# STM32F4_OSD_V13.net
KiCad netlist of a schematic drawn in Altium Designer
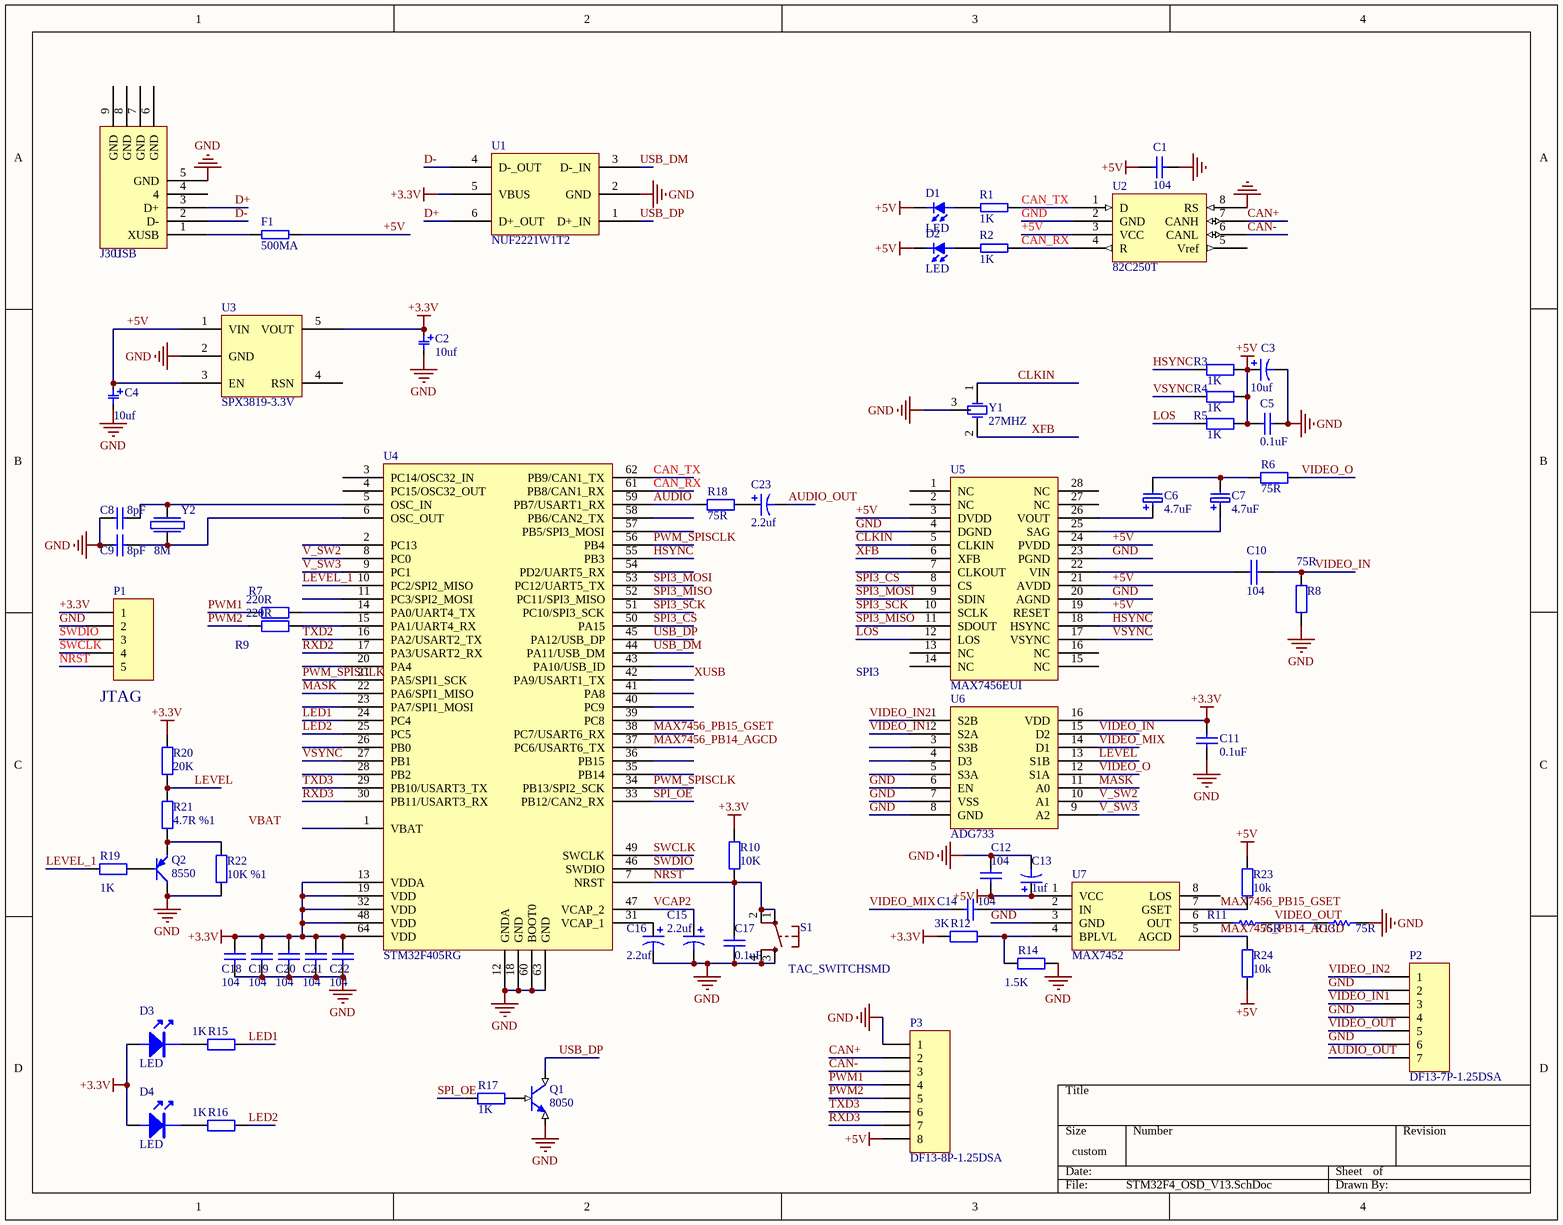
[diagram p0: STM32F4_OSD_V13.SchDoc]

(export (version "E")
  (design (tool "Eeschema 10.0.6"))
  (components
    (comp (ref "C1")
      (value "104")
      (footprint "0603C")
      (description "Capacitor")
      (fields (field (name "PUBLISHER") "Altium Limited"))
      (libsource (lib "*") (part "CAP"))
    )
    (comp (ref "C2") (value "10uf") (footprint "0805") (libsource (lib "电阻电容") (part "ECAP")))
    (comp (ref "C3")
      (value "10uf")
      (footprint "0603C")
      (description "Polarized Capacitor (Radial)")
      (libsource (lib "Miscellaneous Devices") (part "Cap Pol1"))
    )
    (comp (ref "C4") (value "10uf") (footprint "0805") (libsource (lib "电阻电容") (part "ECAP")))
    (comp (ref "C5")
      (value "0.1uF")
      (footprint "0402-CAP")
      (description "Capacitor")
      (fields (field (name "Comment") "Cap") (field (name "PUBLISHER") "Altium Limited"))
      (libsource (lib "Miscellaneous Devices") (part "Cap"))
    )
    (comp (ref "C6")
      (value "4.7uF")
      (footprint "0603C")
      (description "Electrolytic Capacitor 1")
      (libsource (lib "QT_SCH_V2") (part "ELECTRO1"))
    )
    (comp (ref "C7")
      (value "4.7uF")
      (footprint "0603C")
      (description "Electrolytic Capacitor 1")
      (libsource (lib "QT_SCH_V2") (part "ELECTRO1"))
    )
    (comp (ref "C8")
      (value "8pF")
      (footprint "0402-CAP")
      (description "Capacitor")
      (libsource (lib "EMotus Components") (part "CAP0805"))
    )
    (comp (ref "C9")
      (value "8pF")
      (footprint "0402-CAP")
      (description "Capacitor")
      (libsource (lib "EMotus Components") (part "CAP0805"))
    )
    (comp (ref "C10")
      (value "104")
      (footprint "0402-CAP")
      (description "Capacitor")
      (libsource (lib "") (part "CAP_1"))
    )
    (comp (ref "C11")
      (value "0.1uF")
      (footprint "0402-CAP")
      (description "Capacitor")
      (fields (field (name "Comment") "Cap") (field (name "PUBLISHER") "Altium Limited"))
      (libsource (lib "Miscellaneous Devices") (part "Cap"))
    )
    (comp (ref "C12")
      (value "104")
      (footprint "0402-CAP")
      (description "Capacitor")
      (libsource (lib "Miscellaneous Devices") (part "Cap"))
    )
    (comp (ref "C13")
      (value "1uf")
      (footprint "0603C")
      (description "Polarized Capacitor (Radial)")
      (libsource (lib "Miscellaneous Devices") (part "Cap Pol1"))
    )
    (comp (ref "C14")
      (value "104")
      (footprint "0402-CAP")
      (description "Capacitor")
      (libsource (lib "Miscellaneous Devices") (part "Cap"))
    )
    (comp (ref "C15")
      (value "2.2uf")
      (footprint "0603C")
      (description "Polarized Capacitor (Radial)")
      (libsource (lib "Miscellaneous Devices") (part "Cap Pol1"))
    )
    (comp (ref "C16")
      (value "2.2uf")
      (footprint "0603C")
      (description "Polarized Capacitor (Radial)")
      (libsource (lib "Miscellaneous Devices") (part "Cap Pol1"))
    )
    (comp (ref "C17")
      (value "0.1uF")
      (footprint "0402-CAP")
      (description "Capacitor")
      (fields (field (name "Comment") "Cap") (field (name "PUBLISHER") "Altium Limited"))
      (libsource (lib "Miscellaneous Devices") (part "Cap"))
    )
    (comp (ref "C18")
      (value "104")
      (footprint "0402-CAP")
      (description "Capacitor")
      (libsource (lib "Miscellaneous Devices") (part "Cap"))
    )
    (comp (ref "C19")
      (value "104")
      (footprint "0402-CAP")
      (description "Capacitor")
      (libsource (lib "Miscellaneous Devices") (part "Cap"))
    )
    (comp (ref "C20")
      (value "104")
      (footprint "0402-CAP")
      (description "Capacitor")
      (libsource (lib "Miscellaneous Devices") (part "Cap"))
    )
    (comp (ref "C21")
      (value "104")
      (footprint "0402-CAP")
      (description "Capacitor")
      (libsource (lib "Miscellaneous Devices") (part "Cap"))
    )
    (comp (ref "C22")
      (value "104")
      (footprint "0402-CAP")
      (description "Capacitor")
      (libsource (lib "Miscellaneous Devices") (part "Cap"))
    )
    (comp (ref "C23")
      (value "2.2uf")
      (footprint "0603C")
      (description "Polarized Capacitor (Radial)")
      (libsource (lib "Miscellaneous Devices") (part "Cap Pol1"))
    )
    (comp (ref "D1") (value "LED") (footprint "0603-LED") (libsource (lib "原理图库") (part "LED")))
    (comp (ref "D2") (value "LED") (footprint "0603-LED") (libsource (lib "原理图库") (part "LED")))
    (comp (ref "D3") (value "LED") (footprint "0603-LED") (libsource (lib "MySch") (part "LED")))
    (comp (ref "D4") (value "LED") (footprint "0603-LED") (libsource (lib "MySch") (part "LED")))
    (comp (ref "F1") (value "500MA") (footprint "PTC-1206") (libsource (lib "DXP常用原理图库.libsch") (part "RES")))
    (comp (ref "J301")
      (value "USB")
      (footprint "MOLEX_MICRO_USB_AB_BOTTOM_MOUNT")
      (libsource (lib "Schlib1") (part "USB"))
    )
    (comp (ref "P1")
      (value "JTAG")
      (footprint "DF13-5P-1.25DSA")
      (description "Header, 5-Pin")
      (libsource (lib "Miscellaneous Connectors") (part "Header 5"))
    )
    (comp (ref "P2")
      (value "DF13-7P-1.25DSA")
      (footprint "DF13C-7P-1.25V")
      (description "Header, 7-Pin")
      (libsource (lib "Miscellaneous Connectors") (part "Header 7"))
    )
    (comp (ref "P3")
      (value "DF13-8P-1.25DSA")
      (footprint "DF13C-8P-1.25V")
      (description "Header, 8-Pin")
      (libsource (lib "Miscellaneous Connectors") (part "Header 8"))
    )
    (comp (ref "Q1") (value "8050") (footprint "SOT-23") (libsource (lib "原理图库") (part "8050")))
    (comp (ref "Q2")
      (value "8550")
      (footprint "PNP8550")
      (description "PNP Transistor")
      (libsource (lib "DXP常用原理图库.libsch") (part "PNPA"))
    )
    (comp (ref "R1") (value "1K") (footprint "0402-RES") (libsource (lib "DXP常用原理图库.libsch") (part "RES")))
    (comp (ref "R2") (value "1K") (footprint "0402-RES") (libsource (lib "DXP常用原理图库.libsch") (part "RES")))
    (comp (ref "R3")
      (value "1K")
      (footprint "0402-RES")
      (description "Resistor")
      (libsource (lib "") (part "Res2_1"))
    )
    (comp (ref "R4")
      (value "1K")
      (footprint "0402-RES")
      (description "Resistor")
      (libsource (lib "") (part "Res2_1"))
    )
    (comp (ref "R5")
      (value "1K")
      (footprint "0402-RES")
      (description "Resistor")
      (libsource (lib "") (part "Res2_1"))
    )
    (comp (ref "R6")
      (value "75R")
      (footprint "0402-RES")
      (description "Resistor")
      (libsource (lib "") (part "Res2_1"))
    )
    (comp (ref "R7")
      (value "220R")
      (footprint "0402-RES")
      (description "Resistor")
      (libsource (lib "") (part "Res2_2"))
    )
    (comp (ref "R8")
      (value "75R")
      (footprint "0402-RES")
      (description "Resistor")
      (libsource (lib "Miscellaneous Devices") (part "Res2"))
    )
    (comp (ref "R9")
      (value "220R")
      (footprint "0402-RES")
      (description "Resistor")
      (libsource (lib "") (part "Res2_2"))
    )
    (comp (ref "R10")
      (value "10K")
      (footprint "0402-RES")
      (description "Resistor")
      (libsource (lib "Miscellaneous Devices") (part "Res2"))
    )
    (comp (ref "R11")
      (value "75R")
      (footprint "0402-RES")
      (description "Resistor")
      (libsource (lib "Miscellaneous Devices") (part "Res1"))
    )
    (comp (ref "R12")
      (value "3K")
      (footprint "0402-RES")
      (description "Resistor")
      (libsource (lib "") (part "Res2_2"))
    )
    (comp (ref "R13")
      (value "75R")
      (footprint "0402-RES")
      (description "Resistor")
      (libsource (lib "Miscellaneous Devices") (part "Res1"))
    )
    (comp (ref "R14")
      (value "1.5K")
      (footprint "0402-RES")
      (description "Resistor")
      (libsource (lib "") (part "Res2_2"))
    )
    (comp (ref "R15")
      (value "1K")
      (footprint "0402-RES")
      (description "Resistor")
      (libsource (lib "") (part "Res2_2"))
    )
    (comp (ref "R16")
      (value "1K")
      (footprint "0402-RES")
      (description "Resistor")
      (libsource (lib "") (part "Res2_2"))
    )
    (comp (ref "R17")
      (value "1K")
      (footprint "0402-RES")
      (description "Resistor")
      (libsource (lib "") (part "Res2_1"))
    )
    (comp (ref "R18")
      (value "75R")
      (footprint "0402-RES")
      (description "Resistor")
      (libsource (lib "") (part "Res2_2"))
    )
    (comp (ref "R19")
      (value "1K")
      (footprint "0402-RES")
      (description "Resistor")
      (libsource (lib "") (part "Res2_2"))
    )
    (comp (ref "R20")
      (value "20K")
      (footprint "0402-RES")
      (description "Resistor")
      (libsource (lib "") (part "Res2_3"))
    )
    (comp (ref "R21")
      (value "4.7R %1")
      (footprint "0402-RES")
      (description "Resistor")
      (libsource (lib "") (part "Res2_3"))
    )
    (comp (ref "R22")
      (value "10K %1")
      (footprint "0402-RES")
      (description "Resistor")
      (libsource (lib "") (part "Res2_3"))
    )
    (comp (ref "R23")
      (value "10k")
      (footprint "0402-RES")
      (description "Resistor")
      (libsource (lib "") (part "Res2_3"))
    )
    (comp (ref "R24")
      (value "10k")
      (footprint "0402-RES")
      (description "Resistor")
      (libsource (lib "") (part "Res2_3"))
    )
    (comp (ref "S1")
      (value "TAC_SWITCHSMD")
      (footprint "EVQP7J01K")
      (libsource (lib "DIYdrones3") (part "TAC_SWITCHSMD"))
    )
    (comp (ref "U1")
      (value "NUF2221W1T2")
      (footprint "SOT363")
      (libsource (lib "Schlib1") (part "NUF2221W1T2"))
    )
    (comp (ref "U2") (value "82C250T") (footprint "SO-8N") (libsource (lib "*") (part "SN65HVD230D")))
    (comp (ref "U3") (value "SPX3819-3.3V") (footprint "SOT23-5") (libsource (lib "原理图库") (part "SP6201")))
    (comp (ref "U4")
      (value "STM32F405RG")
      (footprint "LQFP64")
      (libsource (lib "Schlib1") (part "STM32F405RG"))
    )
    (comp (ref "U5") (value "MAX7456EUI") (footprint "SSOP-28") (libsource (lib "Schlib1") (part "MAX7456")))
    (comp (ref "U6") (value "ADG733") (footprint "TSOP16") (libsource (lib "Schlib1") (part "ADG733")))
    (comp (ref "U7") (value "MAX7452") (footprint "SOIC-SN8_N") (libsource (lib "Schlib1") (part "MAX7452")))
    (comp (ref "Y1") (value "27MHZ") (footprint "27MHZ") (libsource (lib "晶振滤波器") (part "晶振3脚")))
    (comp (ref "Y2")
      (value "8M")
      (footprint "OSCILLATOR-3.2X2.5")
      (description "7B-8.000MAAJ-T")
      (libsource (lib "passive") (part "ZQ_KX12B"))
    )
  )
  (nets
    (net (code "1") (name "+3.3V") (class "Default")
      (node (ref "C11") (pin "2") (pinfunction "2_2") (pintype "passive"))
      (node (ref "C18") (pin "2") (pinfunction "2_2") (pintype "passive"))
      (node (ref "C19") (pin "2") (pinfunction "2_2") (pintype "passive"))
      (node (ref "C2") (pin "2") (pintype "passive"))
      (node (ref "C20") (pin "2") (pinfunction "2_2") (pintype "passive"))
      (node (ref "C21") (pin "2") (pinfunction "2_2") (pintype "passive"))
      (node (ref "C22") (pin "2") (pinfunction "2_2") (pintype "passive"))
      (node (ref "D3") (pin "1") (pinfunction "1_1") (pintype "passive"))
      (node (ref "D4") (pin "1") (pinfunction "1_1") (pintype "passive"))
      (node (ref "P1") (pin "1") (pinfunction "1_1") (pintype "passive"))
      (node (ref "R10") (pin "2") (pinfunction "2_2") (pintype "passive"))
      (node (ref "R12") (pin "2") (pinfunction "2_2") (pintype "passive"))
      (node (ref "R20") (pin "1") (pinfunction "1_1") (pintype "passive"))
      (node (ref "U1") (pin "5") (pinfunction "VBUS_5") (pintype "passive"))
      (node (ref "U3") (pin "5") (pinfunction "VOUT_5") (pintype "passive"))
      (node (ref "U4") (pin "13") (pinfunction "VDDA_13") (pintype "passive"))
      (node (ref "U4") (pin "19") (pinfunction "VDD_19") (pintype "passive"))
      (node (ref "U4") (pin "32") (pinfunction "VDD_32") (pintype "passive"))
      (node (ref "U4") (pin "48") (pinfunction "VDD_48") (pintype "passive"))
      (node (ref "U4") (pin "64") (pinfunction "VDD_64") (pintype "passive"))
      (node (ref "U6") (pin "16") (pinfunction "VDD_16") (pintype "passive"))
    )
    (net (code "2") (name "+5V") (class "Default")
      (node (ref "C1") (pin "2") (pinfunction "2_2") (pintype "passive"))
      (node (ref "C12") (pin "1") (pinfunction "1_1") (pintype "passive"))
      (node (ref "C13") (pin "1") (pinfunction "1_1") (pintype "passive"))
      (node (ref "C3") (pin "1") (pinfunction "1_1") (pintype "passive"))
      (node (ref "C4") (pin "2") (pintype "passive"))
      (node (ref "C5") (pin "1") (pinfunction "1_1") (pintype "passive"))
      (node (ref "D1") (pin "2") (pinfunction "2_2") (pintype "passive"))
      (node (ref "D2") (pin "2") (pinfunction "2_2") (pintype "passive"))
      (node (ref "F1") (pin "1") (pinfunction "1_1") (pintype "passive"))
      (node (ref "P3") (pin "8") (pinfunction "8_8") (pintype "passive"))
      (node (ref "R23") (pin "1") (pinfunction "1_1") (pintype "passive"))
      (node (ref "R24") (pin "2") (pinfunction "2_2") (pintype "passive"))
      (node (ref "R3") (pin "2") (pinfunction "2_2") (pintype "passive"))
      (node (ref "R4") (pin "2") (pinfunction "2_2") (pintype "passive"))
      (node (ref "R5") (pin "2") (pinfunction "2_2") (pintype "passive"))
      (node (ref "U2") (pin "3") (pinfunction "VCC_3") (pintype "power_in"))
      (node (ref "U3") (pin "1") (pinfunction "VIN_1") (pintype "passive"))
      (node (ref "U3") (pin "3") (pinfunction "EN_3") (pintype "passive"))
      (node (ref "U5") (pin "19") (pinfunction "RESET_19") (pintype "passive"))
      (node (ref "U5") (pin "21") (pinfunction "AVDD_21") (pintype "passive"))
      (node (ref "U5") (pin "24") (pinfunction "PVDD_24") (pintype "passive"))
      (node (ref "U5") (pin "3") (pinfunction "DVDD_3") (pintype "passive"))
      (node (ref "U7") (pin "1") (pinfunction "VCC_1") (pintype "passive"))
    )
    (net (code "3") (name "/AUDIO") (class "Default")
      (node (ref "R18") (pin "2") (pinfunction "2_2") (pintype "passive"))
      (node (ref "U4") (pin "59") (pinfunction "PB7/USART1_RX_59") (pintype "passive"))
    )
    (net (code "4") (name "/AUDIO_OUT") (class "Default")
      (node (ref "C23") (pin "2") (pinfunction "2_2") (pintype "passive"))
      (node (ref "P2") (pin "7") (pinfunction "7_7") (pintype "passive"))
    )
    (net (code "5") (name "/CAN+") (class "Default")
      (node (ref "P3") (pin "2") (pinfunction "2_2") (pintype "passive"))
      (node (ref "U2") (pin "7") (pinfunction "CANH_7") (pintype "bidirectional"))
    )
    (net (code "6") (name "/CAN-") (class "Default")
      (node (ref "P3") (pin "3") (pinfunction "3_3") (pintype "passive"))
      (node (ref "U2") (pin "6") (pinfunction "CANL_6") (pintype "bidirectional"))
    )
    (net (code "7") (name "/CAN_RX") (class "Default")
      (node (ref "R2") (pin "2") (pinfunction "2_2") (pintype "passive"))
      (node (ref "U2") (pin "4") (pinfunction "R_4") (pintype "output"))
      (node (ref "U4") (pin "61") (pinfunction "PB8/CAN1_RX_61") (pintype "passive"))
    )
    (net (code "8") (name "/CAN_TX") (class "Default")
      (node (ref "R1") (pin "2") (pinfunction "2_2") (pintype "passive"))
      (node (ref "U2") (pin "1") (pinfunction "D_1") (pintype "input"))
      (node (ref "U4") (pin "62") (pinfunction "PB9/CAN1_TX_62") (pintype "passive"))
    )
    (net (code "9") (name "/CLKIN") (class "Default")
      (node (ref "U5") (pin "5") (pinfunction "CLKIN_5") (pintype "passive"))
      (node (ref "Y1") (pin "1") (pinfunction "1_1") (pintype "passive"))
    )
    (net (code "10") (name "/D+") (class "Default")
      (node (ref "J301") (pin "3") (pinfunction "D+_3") (pintype "passive"))
      (node (ref "U1") (pin "6") (pinfunction "D+_OUT_6") (pintype "passive"))
    )
    (net (code "11") (name "/D-") (class "Default")
      (node (ref "J301") (pin "2") (pinfunction "D-_2") (pintype "passive"))
      (node (ref "U1") (pin "4") (pinfunction "D-_OUT_4") (pintype "passive"))
    )
    (net (code "12") (name "/HSYNC") (class "Default")
      (node (ref "R3") (pin "1") (pinfunction "1_1") (pintype "passive"))
      (node (ref "U4") (pin "55") (pinfunction "PB3_55") (pintype "passive"))
      (node (ref "U5") (pin "18") (pinfunction "HSYNC_18") (pintype "passive"))
    )
    (net (code "13") (name "/LED1") (class "Default")
      (node (ref "R15") (pin "1") (pinfunction "1_1") (pintype "passive"))
      (node (ref "U4") (pin "24") (pinfunction "PC4_24") (pintype "passive"))
    )
    (net (code "14") (name "/LED2") (class "Default")
      (node (ref "R16") (pin "1") (pinfunction "1_1") (pintype "passive"))
      (node (ref "U4") (pin "25") (pinfunction "PC5_25") (pintype "passive"))
    )
    (net (code "15") (name "/LEVEL") (class "Default")
      (node (ref "R20") (pin "2") (pinfunction "2_2") (pintype "passive"))
      (node (ref "R21") (pin "1") (pinfunction "1_1") (pintype "passive"))
      (node (ref "U6") (pin "13") (pinfunction "S1B_13") (pintype "passive"))
    )
    (net (code "16") (name "/LEVEL_1") (class "Default")
      (node (ref "R19") (pin "2") (pinfunction "2_2") (pintype "passive"))
      (node (ref "U4") (pin "10") (pinfunction "PC2/SPI2_MISO_10") (pintype "passive"))
    )
    (net (code "17") (name "/LOS") (class "Default")
      (node (ref "R5") (pin "1") (pinfunction "1_1") (pintype "passive"))
      (node (ref "U5") (pin "12") (pinfunction "LOS_12") (pintype "passive"))
    )
    (net (code "18") (name "/MASK") (class "Default")
      (node (ref "U4") (pin "22") (pinfunction "PA6/SPI1_MISO_22") (pintype "passive"))
      (node (ref "U6") (pin "11") (pinfunction "A0_11") (pintype "passive"))
    )
    (net (code "19") (name "/MAX7456_PB14_AGCD") (class "Default")
      (node (ref "R24") (pin "1") (pinfunction "1_1") (pintype "passive"))
      (node (ref "U4") (pin "37") (pinfunction "PC6/USART6_TX_37") (pintype "passive"))
      (node (ref "U7") (pin "5") (pinfunction "AGCD_5") (pintype "passive"))
    )
    (net (code "20") (name "/MAX7456_PB15_GSET") (class "Default")
      (node (ref "R23") (pin "2") (pinfunction "2_2") (pintype "passive"))
      (node (ref "U4") (pin "38") (pinfunction "PC7/USART6_RX_38") (pintype "passive"))
      (node (ref "U7") (pin "7") (pinfunction "GSET_7") (pintype "passive"))
    )
    (net (code "21") (name "/NRST") (class "Default")
      (node (ref "C17") (pin "2") (pinfunction "2_2") (pintype "passive"))
      (node (ref "P1") (pin "5") (pinfunction "5_5") (pintype "passive"))
      (node (ref "R10") (pin "1") (pinfunction "1_1") (pintype "passive"))
      (node (ref "S1") (pin "1") (pinfunction "1_1") (pintype "passive"))
      (node (ref "S1") (pin "2") (pinfunction "2_2") (pintype "passive"))
      (node (ref "U4") (pin "7") (pinfunction "NRST_7") (pintype "passive"))
    )
    (net (code "22") (name "/PWM1") (class "Default")
      (node (ref "P3") (pin "4") (pinfunction "4_4") (pintype "passive"))
      (node (ref "R7") (pin "2") (pinfunction "2_2") (pintype "passive"))
    )
    (net (code "23") (name "/PWM2") (class "Default")
      (node (ref "P3") (pin "5") (pinfunction "5_5") (pintype "passive"))
      (node (ref "R9") (pin "2") (pinfunction "2_2") (pintype "passive"))
    )
    (net (code "24") (name "/PWM_SPISCLK") (class "Default")
      (node (ref "U4") (pin "21") (pinfunction "PA5/SPI1_SCK_21") (pintype "passive"))
      (node (ref "U4") (pin "34") (pinfunction "PB13/SPI2_SCK_34") (pintype "passive"))
      (node (ref "U4") (pin "56") (pinfunction "PB4_56") (pintype "passive"))
    )
    (net (code "25") (name "/RXD2") (class "Default")
      (node (ref "U4") (pin "17") (pinfunction "PA3/USART2_RX_17") (pintype "passive"))
    )
    (net (code "26") (name "/RXD3") (class "Default")
      (node (ref "P3") (pin "7") (pinfunction "7_7") (pintype "passive"))
      (node (ref "U4") (pin "30") (pinfunction "PB11/USART3_RX_30") (pintype "passive"))
    )
    (net (code "27") (name "/SPI3_CS") (class "Default")
      (node (ref "U4") (pin "50") (pinfunction "PA15_50") (pintype "passive"))
      (node (ref "U5") (pin "8") (pinfunction "CS_8") (pintype "passive"))
    )
    (net (code "28") (name "/SPI3_MISO") (class "Default")
      (node (ref "U4") (pin "52") (pinfunction "PC11/SPI3_MISO_52") (pintype "passive"))
      (node (ref "U5") (pin "11") (pinfunction "SDOUT_11") (pintype "passive"))
    )
    (net (code "29") (name "/SPI3_MOSI") (class "Default")
      (node (ref "U4") (pin "53") (pinfunction "PC12/UART5_TX_53") (pintype "passive"))
      (node (ref "U5") (pin "9") (pinfunction "SDIN_9") (pintype "passive"))
    )
    (net (code "30") (name "/SPI3_SCK") (class "Default")
      (node (ref "U4") (pin "51") (pinfunction "PC10/SPI3_SCK_51") (pintype "passive"))
      (node (ref "U5") (pin "10") (pinfunction "SCLK_10") (pintype "passive"))
    )
    (net (code "31") (name "/SPI_OE") (class "Default")
      (node (ref "R17") (pin "1") (pinfunction "1_1") (pintype "passive"))
      (node (ref "U4") (pin "33") (pinfunction "PB12/CAN2_RX_33") (pintype "passive"))
    )
    (net (code "32") (name "/SWCLK") (class "Default")
      (node (ref "P1") (pin "4") (pinfunction "4_4") (pintype "passive"))
      (node (ref "U4") (pin "49") (pinfunction "SWCLK_49") (pintype "passive"))
    )
    (net (code "33") (name "/SWDIO") (class "Default")
      (node (ref "P1") (pin "3") (pinfunction "3_3") (pintype "passive"))
      (node (ref "U4") (pin "46") (pinfunction "SWDIO_46") (pintype "passive"))
    )
    (net (code "34") (name "/TXD2") (class "Default")
      (node (ref "U4") (pin "16") (pinfunction "PA2/USART2_TX_16") (pintype "passive"))
    )
    (net (code "35") (name "/TXD3") (class "Default")
      (node (ref "P3") (pin "6") (pinfunction "6_6") (pintype "passive"))
      (node (ref "U4") (pin "29") (pinfunction "PB10/USART3_TX_29") (pintype "passive"))
    )
    (net (code "36") (name "/USB_DM") (class "Default")
      (node (ref "U1") (pin "3") (pinfunction "D-_IN_3") (pintype "passive"))
      (node (ref "U4") (pin "44") (pinfunction "PA11/USB_DM_44") (pintype "passive"))
    )
    (net (code "37") (name "/USB_DP") (class "Default")
      (node (ref "Q1") (pin "3") (pinfunction "C_3") (pintype "input"))
      (node (ref "U1") (pin "1") (pinfunction "D+_IN_1") (pintype "passive"))
      (node (ref "U4") (pin "45") (pinfunction "PA12/USB_DP_45") (pintype "passive"))
    )
    (net (code "39") (name "/VCAP2") (class "Default")
      (node (ref "C15") (pin "1") (pinfunction "1_1") (pintype "passive"))
      (node (ref "U4") (pin "47") (pinfunction "VCAP_2_47") (pintype "passive"))
    )
    (net (code "40") (name "/VIDEO_IN") (class "Default")
      (node (ref "C10") (pin "2") (pinfunction "2_2") (pintype "passive"))
      (node (ref "R8") (pin "2") (pinfunction "2_2") (pintype "passive"))
      (node (ref "U6") (pin "15") (pinfunction "D2_15") (pintype "passive"))
    )
    (net (code "41") (name "/VIDEO_IN1") (class "Default")
      (node (ref "P2") (pin "3") (pinfunction "3_3") (pintype "passive"))
      (node (ref "U6") (pin "2") (pinfunction "S2A_2") (pintype "passive"))
    )
    (net (code "42") (name "/VIDEO_IN2") (class "Default")
      (node (ref "P2") (pin "1") (pinfunction "1_1") (pintype "passive"))
      (node (ref "U6") (pin "1") (pinfunction "S2B_1") (pintype "passive"))
    )
    (net (code "43") (name "/VIDEO_MIX") (class "Default")
      (node (ref "C14") (pin "1") (pinfunction "1_1") (pintype "passive"))
      (node (ref "U6") (pin "14") (pinfunction "D1_14") (pintype "passive"))
    )
    (net (code "44") (name "/VIDEO_O") (class "Default")
      (node (ref "R6") (pin "2") (pinfunction "2_2") (pintype "passive"))
      (node (ref "U6") (pin "12") (pinfunction "S1A_12") (pintype "passive"))
    )
    (net (code "45") (name "/VIDEO_OUT") (class "Default")
      (node (ref "P2") (pin "5") (pinfunction "5_5") (pintype "passive"))
      (node (ref "R11") (pin "1") (pinfunction "1_1") (pintype "passive"))
      (node (ref "R13") (pin "2") (pinfunction "2_2") (pintype "passive"))
    )
    (net (code "46") (name "/VSYNC") (class "Default")
      (node (ref "R4") (pin "1") (pinfunction "1_1") (pintype "passive"))
      (node (ref "U4") (pin "27") (pinfunction "PB1_27") (pintype "passive"))
      (node (ref "U5") (pin "17") (pinfunction "VSYNC_17") (pintype "passive"))
    )
    (net (code "47") (name "/V_SW2") (class "Default")
      (node (ref "U4") (pin "8") (pinfunction "PC0_8") (pintype "passive"))
      (node (ref "U6") (pin "10") (pinfunction "A1_10") (pintype "passive"))
    )
    (net (code "48") (name "/V_SW3") (class "Default")
      (node (ref "U4") (pin "9") (pinfunction "PC1_9") (pintype "passive"))
      (node (ref "U6") (pin "9") (pinfunction "A2_9") (pintype "passive"))
    )
    (net (code "49") (name "/XFB") (class "Default")
      (node (ref "U5") (pin "6") (pinfunction "XFB_6") (pintype "passive"))
      (node (ref "Y1") (pin "2") (pinfunction "2_2") (pintype "passive"))
    )
    (net (code "50") (name "/XUSB") (class "Default")
      (node (ref "U4") (pin "42") (pinfunction "PA9/USART1_TX_42") (pintype "passive"))
    )
    (net (code "51") (name "GND") (class "Default")
      (node (ref "C1") (pin "1") (pinfunction "1_1") (pintype "passive"))
      (node (ref "C11") (pin "1") (pinfunction "1_1") (pintype "passive"))
      (node (ref "C12") (pin "2") (pinfunction "2_2") (pintype "passive"))
      (node (ref "C13") (pin "2") (pinfunction "2_2") (pintype "passive"))
      (node (ref "C15") (pin "2") (pinfunction "2_2") (pintype "passive"))
      (node (ref "C16") (pin "2") (pinfunction "2_2") (pintype "passive"))
      (node (ref "C17") (pin "1") (pinfunction "1_1") (pintype "passive"))
      (node (ref "C18") (pin "1") (pinfunction "1_1") (pintype "passive"))
      (node (ref "C19") (pin "1") (pinfunction "1_1") (pintype "passive"))
      (node (ref "C2") (pin "1") (pintype "passive"))
      (node (ref "C20") (pin "1") (pinfunction "1_1") (pintype "passive"))
      (node (ref "C21") (pin "1") (pinfunction "1_1") (pintype "passive"))
      (node (ref "C22") (pin "1") (pinfunction "1_1") (pintype "passive"))
      (node (ref "C3") (pin "2") (pinfunction "2_2") (pintype "passive"))
      (node (ref "C4") (pin "1") (pintype "passive"))
      (node (ref "C5") (pin "2") (pinfunction "2_2") (pintype "passive"))
      (node (ref "C8") (pin "2") (pinfunction "2_2") (pintype "passive"))
      (node (ref "C9") (pin "2") (pinfunction "2_2") (pintype "passive"))
      (node (ref "J301") (pin "5") (pinfunction "GND_5") (pintype "passive"))
      (node (ref "P1") (pin "2") (pinfunction "2_2") (pintype "passive"))
      (node (ref "P2") (pin "2") (pinfunction "2_2") (pintype "passive"))
      (node (ref "P2") (pin "4") (pinfunction "4_4") (pintype "passive"))
      (node (ref "P2") (pin "6") (pinfunction "6_6") (pintype "passive"))
      (node (ref "P3") (pin "1") (pinfunction "1_1") (pintype "passive"))
      (node (ref "Q1") (pin "2") (pinfunction "E_2") (pintype "input"))
      (node (ref "Q2") (pin "3") (pinfunction "C_3") (pintype "passive"))
      (node (ref "R13") (pin "1") (pinfunction "1_1") (pintype "passive"))
      (node (ref "R14") (pin "1") (pinfunction "1_1") (pintype "passive"))
      (node (ref "R22") (pin "2") (pinfunction "2_2") (pintype "passive"))
      (node (ref "R8") (pin "1") (pinfunction "1_1") (pintype "passive"))
      (node (ref "S1") (pin "3") (pinfunction "3_3") (pintype "passive"))
      (node (ref "S1") (pin "4") (pinfunction "4_4") (pintype "passive"))
      (node (ref "U1") (pin "2") (pinfunction "GND_2") (pintype "passive"))
      (node (ref "U2") (pin "2") (pinfunction "GND_2") (pintype "power_in"))
      (node (ref "U2") (pin "8") (pinfunction "RS_8") (pintype "input"))
      (node (ref "U3") (pin "2") (pinfunction "GND_2") (pintype "passive"))
      (node (ref "U4") (pin "12") (pinfunction "GNDA_12") (pintype "passive"))
      (node (ref "U4") (pin "18") (pinfunction "GND_18") (pintype "passive"))
      (node (ref "U4") (pin "60") (pinfunction "BOOT0_60") (pintype "passive"))
      (node (ref "U4") (pin "63") (pinfunction "GND_63") (pintype "passive"))
      (node (ref "U5") (pin "20") (pinfunction "AGND_20") (pintype "passive"))
      (node (ref "U5") (pin "23") (pinfunction "PGND_23") (pintype "passive"))
      (node (ref "U5") (pin "4") (pinfunction "DGND_4") (pintype "passive"))
      (node (ref "U6") (pin "6") (pinfunction "EN_6") (pintype "passive"))
      (node (ref "U6") (pin "7") (pinfunction "VSS_7") (pintype "passive"))
      (node (ref "U6") (pin "8") (pinfunction "GND_8") (pintype "passive"))
      (node (ref "U7") (pin "3") (pinfunction "GND_3") (pintype "passive"))
      (node (ref "Y1") (pin "3") (pinfunction "3_3") (pintype "passive"))
    )
    (net (code "52") (name "Net-(C6-Pad2)") (class "Default")
      (node (ref "C6") (pin "2") (pinfunction "2_2") (pintype "passive"))
      (node (ref "C7") (pin "2") (pinfunction "2_2") (pintype "passive"))
      (node (ref "R6") (pin "1") (pinfunction "1_1") (pintype "passive"))
    )
    (net (code "53") (name "Net-(C23-Pad1)") (class "Default")
      (node (ref "C23") (pin "1") (pinfunction "1_1") (pintype "passive"))
      (node (ref "R18") (pin "1") (pinfunction "1_1") (pintype "passive"))
    )
    (net (code "54") (name "Net-(D1-Pad1)") (class "Default")
      (node (ref "D1") (pin "1") (pinfunction "1_1") (pintype "passive"))
      (node (ref "R1") (pin "1") (pinfunction "1_1") (pintype "passive"))
    )
    (net (code "55") (name "Net-(D2-Pad1)") (class "Default")
      (node (ref "D2") (pin "1") (pinfunction "1_1") (pintype "passive"))
      (node (ref "R2") (pin "1") (pinfunction "1_1") (pintype "passive"))
    )
    (net (code "56") (name "Net-(D3-Pad2)") (class "Default")
      (node (ref "D3") (pin "2") (pinfunction "2_2") (pintype "passive"))
      (node (ref "R15") (pin "2") (pinfunction "2_2") (pintype "passive"))
    )
    (net (code "57") (name "Net-(D4-Pad2)") (class "Default")
      (node (ref "D4") (pin "2") (pinfunction "2_2") (pintype "passive"))
      (node (ref "R16") (pin "2") (pinfunction "2_2") (pintype "passive"))
    )
    (net (code "58") (name "Net-(J301-XUSB)") (class "Default")
      (node (ref "F1") (pin "2") (pinfunction "2_2") (pintype "passive"))
      (node (ref "J301") (pin "1") (pinfunction "XUSB_1") (pintype "passive"))
    )
    (net (code "59") (name "Net-(Q1-B)") (class "Default")
      (node (ref "Q1") (pin "1") (pinfunction "B_1") (pintype "input"))
      (node (ref "R17") (pin "2") (pinfunction "2_2") (pintype "passive"))
    )
    (net (code "60") (name "Net-(Q2-B)") (class "Default")
      (node (ref "Q2") (pin "2") (pinfunction "B_2") (pintype "passive"))
      (node (ref "R19") (pin "1") (pinfunction "1_1") (pintype "passive"))
    )
    (net (code "61") (name "Net-(Q2-E)") (class "Default")
      (node (ref "Q2") (pin "1") (pinfunction "E_1") (pintype "passive"))
      (node (ref "R21") (pin "2") (pinfunction "2_2") (pintype "passive"))
      (node (ref "R22") (pin "1") (pinfunction "1_1") (pintype "passive"))
    )
    (net (code "62") (name "Net-(U4-OSC_IN)") (class "Default")
      (node (ref "C8") (pin "1") (pinfunction "1_1") (pintype "passive"))
      (node (ref "U4") (pin "5") (pinfunction "OSC_IN_5") (pintype "passive"))
      (node (ref "Y2") (pin "1") (pinfunction "1_1") (pintype "passive"))
    )
    (net (code "63") (name "Net-(U4-OSC_OUT)") (class "Default")
      (node (ref "C9") (pin "1") (pinfunction "1_1") (pintype "passive"))
      (node (ref "U4") (pin "6") (pinfunction "OSC_OUT_6") (pintype "passive"))
      (node (ref "Y2") (pin "2") (pinfunction "2_2") (pintype "passive"))
    )
    (net (code "64") (name "Net-(U4-PA0{slash}UART4_TX)") (class "Default")
      (node (ref "R7") (pin "1") (pinfunction "1_1") (pintype "passive"))
      (node (ref "U4") (pin "14") (pinfunction "PA0/UART4_TX_14") (pintype "passive"))
    )
    (net (code "65") (name "Net-(U4-PA1{slash}UART4_RX)") (class "Default")
      (node (ref "R9") (pin "1") (pinfunction "1_1") (pintype "passive"))
      (node (ref "U4") (pin "15") (pinfunction "PA1/UART4_RX_15") (pintype "passive"))
    )
    (net (code "66") (name "Net-(U4-VCAP_1)") (class "Default")
      (node (ref "C16") (pin "1") (pinfunction "1_1") (pintype "passive"))
      (node (ref "U4") (pin "31") (pinfunction "VCAP_1_31") (pintype "passive"))
    )
    (net (code "67") (name "Net-(U5-SAG)") (class "Default")
      (node (ref "C7") (pin "1") (pinfunction "1_1") (pintype "passive"))
      (node (ref "U5") (pin "25") (pinfunction "SAG_25") (pintype "passive"))
    )
    (net (code "68") (name "Net-(U5-VIN)") (class "Default")
      (node (ref "C10") (pin "1") (pinfunction "1_1") (pintype "passive"))
      (node (ref "U5") (pin "22") (pinfunction "VIN_22") (pintype "passive"))
    )
    (net (code "69") (name "Net-(U5-VOUT)") (class "Default")
      (node (ref "C6") (pin "1") (pinfunction "1_1") (pintype "passive"))
      (node (ref "U5") (pin "26") (pinfunction "VOUT_26") (pintype "passive"))
    )
    (net (code "70") (name "Net-(U7-BPLVL)") (class "Default")
      (node (ref "R12") (pin "1") (pinfunction "1_1") (pintype "passive"))
      (node (ref "R14") (pin "2") (pinfunction "2_2") (pintype "passive"))
      (node (ref "U7") (pin "4") (pinfunction "BPLVL_4") (pintype "passive"))
    )
    (net (code "71") (name "Net-(U7-IN)") (class "Default")
      (node (ref "C14") (pin "2") (pinfunction "2_2") (pintype "passive"))
      (node (ref "U7") (pin "2") (pinfunction "IN_2") (pintype "passive"))
    )
    (net (code "72") (name "Net-(U7-OUT)") (class "Default")
      (node (ref "R11") (pin "2") (pinfunction "2_2") (pintype "passive"))
      (node (ref "U7") (pin "6") (pinfunction "OUT_6") (pintype "passive"))
    )
    (net (code "73") (name "unconnected-(J301-GND-Pad6)") (class "Default")
      (node (ref "J301") (pin "6") (pinfunction "GND_6") (pintype "passive"))
    )
    (net (code "74") (name "unconnected-(J301-GND-Pad7)") (class "Default")
      (node (ref "J301") (pin "7") (pinfunction "GND_7") (pintype "passive"))
    )
    (net (code "75") (name "unconnected-(J301-GND-Pad8)") (class "Default")
      (node (ref "J301") (pin "8") (pinfunction "GND_8") (pintype "passive"))
    )
    (net (code "76") (name "unconnected-(J301-GND-Pad9)") (class "Default")
      (node (ref "J301") (pin "9") (pinfunction "GND_9") (pintype "passive"))
    )
    (net (code "77") (name "unconnected-(J301-Pad4)") (class "Default")
      (node (ref "J301") (pin "4") (pinfunction "4_4") (pintype "passive"))
    )
    (net (code "78") (name "unconnected-(U2-Vref-Pad5)") (class "Default")
      (node (ref "U2") (pin "5") (pinfunction "Vref_5") (pintype "output"))
    )
    (net (code "79") (name "unconnected-(U3-RSN-Pad4)") (class "Default")
      (node (ref "U3") (pin "4") (pinfunction "RSN_4") (pintype "passive"))
    )
    (net (code "80") (name "unconnected-(U4-PA4-Pad20)") (class "Default")
      (node (ref "U4") (pin "20") (pinfunction "PA4_20") (pintype "passive"))
    )
    (net (code "81") (name "unconnected-(U4-PA7{slash}SPI1_MOSI-Pad23)") (class "Default")
      (node (ref "U4") (pin "23") (pinfunction "PA7/SPI1_MOSI_23") (pintype "passive"))
    )
    (net (code "82") (name "unconnected-(U4-PA8-Pad41)") (class "Default")
      (node (ref "U4") (pin "41") (pinfunction "PA8_41") (pintype "passive"))
    )
    (net (code "83") (name "unconnected-(U4-PA10{slash}USB_ID-Pad43)") (class "Default")
      (node (ref "U4") (pin "43") (pinfunction "PA10/USB_ID_43") (pintype "passive"))
    )
    (net (code "84") (name "unconnected-(U4-PB0-Pad26)") (class "Default")
      (node (ref "U4") (pin "26") (pinfunction "PB0_26") (pintype "passive"))
    )
    (net (code "85") (name "unconnected-(U4-PB2-Pad28)") (class "Default")
      (node (ref "U4") (pin "28") (pinfunction "PB2_28") (pintype "passive"))
    )
    (net (code "86") (name "unconnected-(U4-PB5{slash}SPI3_MOSI-Pad57)") (class "Default")
      (node (ref "U4") (pin "57") (pinfunction "PB5/SPI3_MOSI_57") (pintype "passive"))
    )
    (net (code "87") (name "unconnected-(U4-PB6{slash}CAN2_TX-Pad58)") (class "Default")
      (node (ref "U4") (pin "58") (pinfunction "PB6/CAN2_TX_58") (pintype "passive"))
    )
    (net (code "88") (name "unconnected-(U4-PB14-Pad35)") (class "Default")
      (node (ref "U4") (pin "35") (pinfunction "PB14_35") (pintype "passive"))
    )
    (net (code "89") (name "unconnected-(U4-PB15-Pad36)") (class "Default")
      (node (ref "U4") (pin "36") (pinfunction "PB15_36") (pintype "passive"))
    )
    (net (code "90") (name "unconnected-(U4-PC3{slash}SPI2_MOSI-Pad11)") (class "Default")
      (node (ref "U4") (pin "11") (pinfunction "PC3/SPI2_MOSI_11") (pintype "passive"))
    )
    (net (code "91") (name "unconnected-(U4-PC8-Pad39)") (class "Default")
      (node (ref "U4") (pin "39") (pinfunction "PC8_39") (pintype "passive"))
    )
    (net (code "92") (name "unconnected-(U4-PC9-Pad40)") (class "Default")
      (node (ref "U4") (pin "40") (pinfunction "PC9_40") (pintype "passive"))
    )
    (net (code "93") (name "unconnected-(U4-PC13-Pad2)") (class "Default")
      (node (ref "U4") (pin "2") (pinfunction "PC13_2") (pintype "passive"))
    )
    (net (code "94") (name "unconnected-(U4-PC14{slash}OSC32_IN-Pad3)") (class "Default")
      (node (ref "U4") (pin "3") (pinfunction "PC14/OSC32_IN_3") (pintype "passive"))
    )
    (net (code "95") (name "unconnected-(U4-PC15{slash}OSC32_OUT-Pad4)") (class "Default")
      (node (ref "U4") (pin "4") (pinfunction "PC15/OSC32_OUT_4") (pintype "passive"))
    )
    (net (code "96") (name "unconnected-(U4-PD2{slash}UART5_RX-Pad54)") (class "Default")
      (node (ref "U4") (pin "54") (pinfunction "PD2/UART5_RX_54") (pintype "passive"))
    )
    (net (code "97") (name "unconnected-(U4-VBAT-Pad1)") (class "Default")
      (node (ref "U4") (pin "1") (pinfunction "VBAT_1") (pintype "passive"))
    )
    (net (code "98") (name "unconnected-(U5-CLKOUT-Pad7)") (class "Default")
      (node (ref "U5") (pin "7") (pinfunction "CLKOUT_7") (pintype "passive"))
    )
    (net (code "99") (name "unconnected-(U5-NC-Pad1)") (class "Default")
      (node (ref "U5") (pin "1") (pinfunction "NC_1") (pintype "passive"))
    )
    (net (code "100") (name "unconnected-(U5-NC-Pad2)") (class "Default")
      (node (ref "U5") (pin "2") (pinfunction "NC_2") (pintype "passive"))
    )
    (net (code "101") (name "unconnected-(U5-NC-Pad13)") (class "Default")
      (node (ref "U5") (pin "13") (pinfunction "NC_13") (pintype "passive"))
    )
    (net (code "102") (name "unconnected-(U5-NC-Pad14)") (class "Default")
      (node (ref "U5") (pin "14") (pinfunction "NC_14") (pintype "passive"))
    )
    (net (code "103") (name "unconnected-(U5-NC-Pad15)") (class "Default")
      (node (ref "U5") (pin "15") (pinfunction "NC_15") (pintype "passive"))
    )
    (net (code "104") (name "unconnected-(U5-NC-Pad16)") (class "Default")
      (node (ref "U5") (pin "16") (pinfunction "NC_16") (pintype "passive"))
    )
    (net (code "105") (name "unconnected-(U5-NC-Pad27)") (class "Default")
      (node (ref "U5") (pin "27") (pinfunction "NC_27") (pintype "passive"))
    )
    (net (code "106") (name "unconnected-(U5-NC-Pad28)") (class "Default")
      (node (ref "U5") (pin "28") (pinfunction "NC_28") (pintype "passive"))
    )
    (net (code "107") (name "unconnected-(U6-D3-Pad4)") (class "Default")
      (node (ref "U6") (pin "4") (pinfunction "D3_4") (pintype "passive"))
    )
    (net (code "108") (name "unconnected-(U6-S3A-Pad5)") (class "Default")
      (node (ref "U6") (pin "5") (pinfunction "S3A_5") (pintype "passive"))
    )
    (net (code "109") (name "unconnected-(U6-S3B-Pad3)") (class "Default")
      (node (ref "U6") (pin "3") (pinfunction "S3B_3") (pintype "passive"))
    )
    (net (code "110") (name "unconnected-(U7-LOS-Pad8)") (class "Default")
      (node (ref "U7") (pin "8") (pinfunction "LOS_8") (pintype "passive"))
    )
  )
)
